# stm32103c8t6-v5.net
KiCad netlist of a schematic drawn in EAGLE
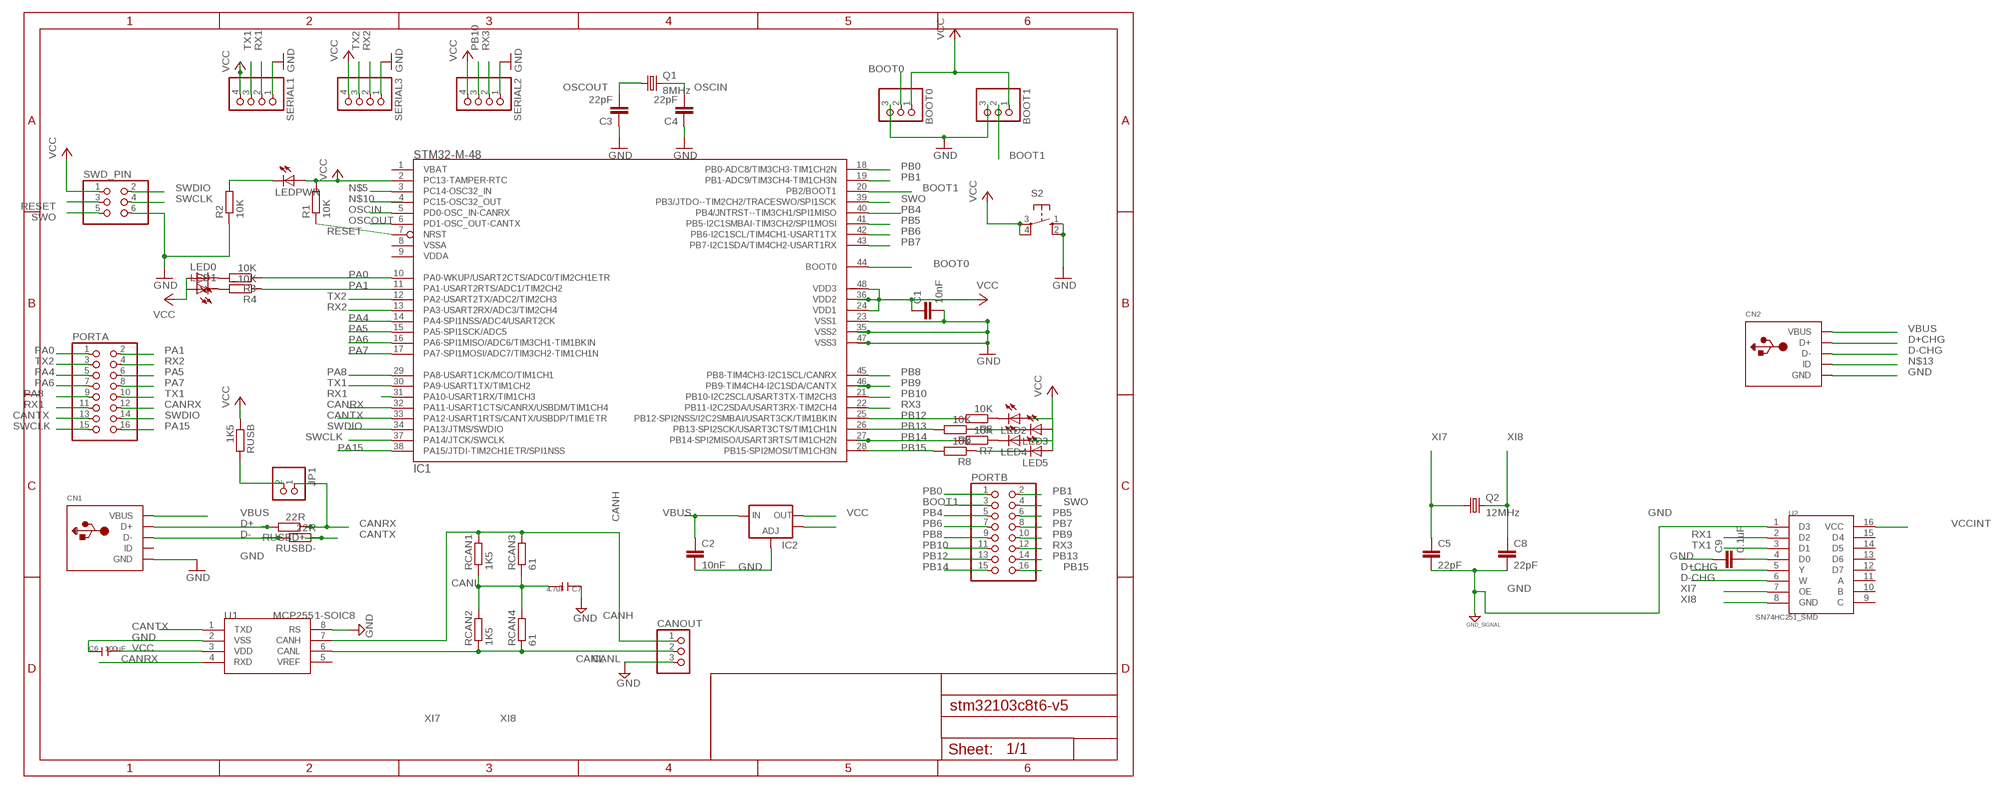
[diagram p0: schematic, sheet 1]

(export (version "E")
  (design (tool "Eeschema 10.0.6"))
  (components
    (comp (ref "BOOT0")
      (value "PINHD-1X3")
      (footprint "eagle-import:1X03")
      (libsource (lib "eagle-import") (part "PINHD-1X3"))
    )
    (comp (ref "BOOT1")
      (value "PINHD-1X3")
      (footprint "eagle-import:1X03")
      (libsource (lib "eagle-import") (part "PINHD-1X3"))
    )
    (comp (ref "C1")
      (value "10nF")
      (footprint "eagle-import:C1210")
      (libsource (lib "eagle-import") (part "C-EUC1210"))
    )
    (comp (ref "C2")
      (value "10nF")
      (footprint "eagle-import:C1206")
      (libsource (lib "eagle-import") (part "C-EUC1206"))
    )
    (comp (ref "C3")
      (value "22pF")
      (footprint "eagle-import:C1210")
      (libsource (lib "eagle-import") (part "C-EUC1210"))
    )
    (comp (ref "C4")
      (value "22pF")
      (footprint "eagle-import:C1210")
      (libsource (lib "eagle-import") (part "C-EUC1210"))
    )
    (comp (ref "C5")
      (value "22pF")
      (footprint "eagle-import:C1206")
      (libsource (lib "eagle-import") (part "C-EUC1206"))
    )
    (comp (ref "C6")
      (value "100uF")
      (footprint "eagle-import:C1206")
      (libsource (lib "eagle-import") (part "C-1206"))
    )
    (comp (ref "C7")
      (value "4.7uF")
      (footprint "eagle-import:C1206")
      (libsource (lib "eagle-import") (part "C-1206"))
    )
    (comp (ref "C8")
      (value "22pF")
      (footprint "eagle-import:C1206")
      (libsource (lib "eagle-import") (part "C-EUC1206"))
    )
    (comp (ref "C9")
      (value "0.1uF")
      (footprint "eagle-import:C1206")
      (libsource (lib "eagle-import") (part "C-EUC1206"))
    )
    (comp (ref "CANOUT")
      (value "PINHD-1X3")
      (footprint "eagle-import:1X03")
      (libsource (lib "eagle-import") (part "PINHD-1X3"))
    )
    (comp (ref "CN1")
      (value "USBTHM")
      (footprint "eagle-import:USB-MINIB-THM")
      (libsource (lib "eagle-import") (part "USBTHM"))
    )
    (comp (ref "CN2")
      (value "USBTHM")
      (footprint "eagle-import:USB-MINIB-THM")
      (libsource (lib "eagle-import") (part "USBTHM"))
    )
    (comp (ref "IC1")
      (value "STM32-M-48")
      (footprint "eagle-import:LQFP48")
      (libsource (lib "eagle-import") (part "STM32-M-48"))
    )
    (comp (ref "IC2")
      (value "V_REG_LM1117SOT223")
      (footprint "eagle-import:SOT223")
      (libsource (lib "eagle-import") (part "V_REG_LM1117SOT223"))
    )
    (comp (ref "JP1")
      (value "PINHD-1X2")
      (footprint "eagle-import:1X02")
      (libsource (lib "eagle-import") (part "PINHD-1X2"))
    )
    (comp (ref "LED0")
      (value "LEDSMT1206")
      (footprint "eagle-import:1206")
      (libsource (lib "eagle-import") (part "LEDSMT1206"))
    )
    (comp (ref "LED1")
      (value "LEDSMT1206")
      (footprint "eagle-import:1206")
      (libsource (lib "eagle-import") (part "LEDSMT1206"))
    )
    (comp (ref "LED2")
      (value "LEDSMT1206")
      (footprint "eagle-import:1206")
      (libsource (lib "eagle-import") (part "LEDSMT1206"))
    )
    (comp (ref "LED3")
      (value "LEDSMT1206")
      (footprint "eagle-import:1206")
      (libsource (lib "eagle-import") (part "LEDSMT1206"))
    )
    (comp (ref "LED4")
      (value "LEDSMT1206")
      (footprint "eagle-import:1206")
      (libsource (lib "eagle-import") (part "LEDSMT1206"))
    )
    (comp (ref "LED5")
      (value "LEDSMT1206")
      (footprint "eagle-import:1206")
      (libsource (lib "eagle-import") (part "LEDSMT1206"))
    )
    (comp (ref "LEDPWR")
      (value "LEDSMT1206")
      (footprint "eagle-import:1206")
      (libsource (lib "eagle-import") (part "LEDSMT1206"))
    )
    (comp (ref "PORTA")
      (value "PINHD-2X8")
      (footprint "eagle-import:2X08")
      (libsource (lib "eagle-import") (part "PINHD-2X8"))
    )
    (comp (ref "PORTB")
      (value "PINHD-2X8")
      (footprint "eagle-import:2X08")
      (libsource (lib "eagle-import") (part "PINHD-2X8"))
    )
    (comp (ref "Q1")
      (value "8MHz")
      (footprint "eagle-import:HC49_S")
      (libsource (lib "eagle-import") (part "CRYSTALHC49S"))
    )
    (comp (ref "Q2")
      (value "12MHz")
      (footprint "eagle-import:HC49_S")
      (libsource (lib "eagle-import") (part "CRYSTALHC49S"))
    )
    (comp (ref "R1")
      (value "10K")
      (footprint "eagle-import:R1206")
      (libsource (lib "eagle-import") (part "R-EU_R1206"))
    )
    (comp (ref "R2")
      (value "10K")
      (footprint "eagle-import:R1206")
      (libsource (lib "eagle-import") (part "R-EU_R1206"))
    )
    (comp (ref "R3")
      (value "10K")
      (footprint "eagle-import:R1206")
      (libsource (lib "eagle-import") (part "R-EU_R1206"))
    )
    (comp (ref "R4")
      (value "10K")
      (footprint "eagle-import:R1206")
      (libsource (lib "eagle-import") (part "R-EU_R1206"))
    )
    (comp (ref "R5")
      (value "10K")
      (footprint "eagle-import:R1206")
      (libsource (lib "eagle-import") (part "R-EU_R1206"))
    )
    (comp (ref "R6")
      (value "10K")
      (footprint "eagle-import:R1206")
      (libsource (lib "eagle-import") (part "R-EU_R1206"))
    )
    (comp (ref "R7")
      (value "10K")
      (footprint "eagle-import:R1206")
      (libsource (lib "eagle-import") (part "R-EU_R1206"))
    )
    (comp (ref "R8")
      (value "10K")
      (footprint "eagle-import:R1206")
      (libsource (lib "eagle-import") (part "R-EU_R1206"))
    )
    (comp (ref "RCAN1")
      (value "1K5")
      (footprint "eagle-import:R1206")
      (libsource (lib "eagle-import") (part "R-EU_R1206"))
    )
    (comp (ref "RCAN2")
      (value "1K5")
      (footprint "eagle-import:R1206")
      (libsource (lib "eagle-import") (part "R-EU_R1206"))
    )
    (comp (ref "RCAN3")
      (value "61")
      (footprint "eagle-import:R1206")
      (libsource (lib "eagle-import") (part "R-EU_R1206"))
    )
    (comp (ref "RCAN4")
      (value "61")
      (footprint "eagle-import:R1206")
      (libsource (lib "eagle-import") (part "R-EU_R1206"))
    )
    (comp (ref "RUSB")
      (value "1K5")
      (footprint "eagle-import:R1206")
      (libsource (lib "eagle-import") (part "R-EU_R1206"))
    )
    (comp (ref "RUSBD+")
      (value "22R")
      (footprint "eagle-import:R1206")
      (libsource (lib "eagle-import") (part "R-EU_R1206"))
    )
    (comp (ref "RUSBD-")
      (value "22R")
      (footprint "eagle-import:R1206")
      (libsource (lib "eagle-import") (part "R-EU_R1206"))
    )
    (comp (ref "S2")
      (value "10-XX")
      (footprint "eagle-import:B3F-10XX")
      (fields (field (name "MPN") "B3F-1000"))
      (libsource (lib "eagle-import") (part "10-XX"))
    )
    (comp (ref "SERIAL1")
      (value "PINHD-1X4")
      (footprint "eagle-import:1X04")
      (libsource (lib "eagle-import") (part "PINHD-1X4"))
    )
    (comp (ref "SERIAL2")
      (value "PINHD-1X4")
      (footprint "eagle-import:1X04")
      (libsource (lib "eagle-import") (part "PINHD-1X4"))
    )
    (comp (ref "SERIAL3")
      (value "PINHD-1X4")
      (footprint "eagle-import:1X04")
      (libsource (lib "eagle-import") (part "PINHD-1X4"))
    )
    (comp (ref "SWD_PIN")
      (value "PINHD-2X3")
      (footprint "eagle-import:2X03")
      (libsource (lib "eagle-import") (part "PINHD-2X3"))
    )
    (comp (ref "U1")
      (value "MCP2551-SOIC8")
      (footprint "eagle-import:SOIC8-6.0")
      (libsource (lib "eagle-import") (part "MCP2551-SOIC8"))
    )
    (comp (ref "U2")
      (value "SN74HC251_SMD")
      (footprint "eagle-import:SO016")
      (libsource (lib "eagle-import") (part "SN74HC251_SMD"))
    )
  )
  (nets
    (net (code "1") (name "/BOOT0") (class "Default")
      (node (ref "BOOT0") (pin "2") (pinfunction "2_2") (pintype "passive"))
      (node (ref "IC1") (pin "44") (pinfunction "BOOT0_44") (pintype "input"))
    )
    (net (code "2") (name "/BOOT1") (class "Default")
      (node (ref "BOOT1") (pin "2") (pinfunction "2_2") (pintype "passive"))
      (node (ref "IC1") (pin "20") (pinfunction "PB2/BOOT1_20") (pintype "bidirectional"))
      (node (ref "PORTB") (pin "3") (pinfunction "3_3") (pintype "passive"))
    )
    (net (code "3") (name "/CANH") (class "Default")
      (node (ref "CANOUT") (pin "1") (pinfunction "1_1") (pintype "passive"))
      (node (ref "RCAN1") (pin "2") (pinfunction "2_2") (pintype "passive"))
      (node (ref "RCAN3") (pin "2") (pinfunction "2_2") (pintype "passive"))
      (node (ref "U1") (pin "7") (pinfunction "CANH_7") (pintype "bidirectional"))
    )
    (net (code "4") (name "/CANL") (class "Default")
      (node (ref "CANOUT") (pin "2") (pinfunction "2_2") (pintype "passive"))
      (node (ref "RCAN2") (pin "1") (pinfunction "1_1") (pintype "passive"))
      (node (ref "RCAN4") (pin "1") (pinfunction "1_1") (pintype "passive"))
      (node (ref "U1") (pin "6") (pinfunction "CANL_6") (pintype "bidirectional"))
    )
    (net (code "5") (name "/CANRX") (class "Default")
      (node (ref "IC1") (pin "32") (pinfunction "PA11-USART1CTS/CANRX/USBDM/TIM1CH4_32") (pintype "bidirectional"))
      (node (ref "JP1") (pin "1") (pinfunction "1_1") (pintype "passive"))
      (node (ref "PORTA") (pin "12") (pinfunction "12_12") (pintype "passive"))
      (node (ref "RUSBD+") (pin "1") (pinfunction "1_1") (pintype "passive"))
      (node (ref "U1") (pin "4") (pinfunction "RXD_4") (pintype "bidirectional"))
    )
    (net (code "6") (name "/CANTX") (class "Default")
      (node (ref "IC1") (pin "33") (pinfunction "PA12-USART1RTS/CANTX/USBDP/TIM1ETR_33") (pintype "bidirectional"))
      (node (ref "PORTA") (pin "13") (pinfunction "13_13") (pintype "passive"))
      (node (ref "RUSBD-") (pin "1") (pinfunction "1_1") (pintype "passive"))
      (node (ref "U1") (pin "1") (pinfunction "TXD_1") (pintype "bidirectional"))
    )
    (net (code "7") (name "/D+") (class "Default")
      (node (ref "CN1") (pin "D+") (pinfunction "D+_D+") (pintype "bidirectional"))
      (node (ref "RUSBD+") (pin "2") (pinfunction "2_2") (pintype "passive"))
    )
    (net (code "8") (name "/D+CHG") (class "Default")
      (node (ref "CN2") (pin "D+") (pinfunction "D+_D+") (pintype "bidirectional"))
      (node (ref "U2") (pin "5") (pinfunction "Y_5") (pintype "bidirectional"))
    )
    (net (code "9") (name "/D-") (class "Default")
      (node (ref "CN1") (pin "D-") (pinfunction "D-_D-") (pintype "bidirectional"))
      (node (ref "RUSBD-") (pin "2") (pinfunction "2_2") (pintype "passive"))
    )
    (net (code "10") (name "/D-CHG") (class "Default")
      (node (ref "CN2") (pin "D-") (pinfunction "D-_D-") (pintype "bidirectional"))
      (node (ref "U2") (pin "6") (pinfunction "W_6") (pintype "bidirectional"))
    )
    (net (code "11") (name "/N$5") (class "Default")
      (node (ref "IC1") (pin "3") (pinfunction "PC14-OSC32_IN_3") (pintype "bidirectional"))
    )
    (net (code "13") (name "/N$13") (class "Default")
      (node (ref "CN2") (pin "ID") (pinfunction "ID_ID") (pintype "bidirectional"))
    )
    (net (code "14") (name "/OSCIN") (class "Default")
      (node (ref "C4") (pin "2") (pinfunction "2_2") (pintype "passive"))
      (node (ref "IC1") (pin "5") (pinfunction "PD0-OSC_IN-CANRX_5") (pintype "input"))
      (node (ref "Q1") (pin "2") (pinfunction "2_2") (pintype "passive"))
    )
    (net (code "15") (name "/OSCOUT") (class "Default")
      (node (ref "C3") (pin "2") (pinfunction "2_2") (pintype "passive"))
      (node (ref "IC1") (pin "6") (pinfunction "PD1-OSC_OUT-CANTX_6") (pintype "output"))
      (node (ref "Q1") (pin "1") (pinfunction "1_1") (pintype "passive"))
    )
    (net (code "16") (name "/PA0") (class "Default")
      (node (ref "IC1") (pin "10") (pinfunction "PA0-WKUP/USART2CTS/ADC0/TIM2CH1ETR_10") (pintype "bidirectional"))
      (node (ref "PORTA") (pin "1") (pinfunction "1_1") (pintype "passive"))
      (node (ref "R3") (pin "1") (pinfunction "1_1") (pintype "passive"))
    )
    (net (code "17") (name "/PA1") (class "Default")
      (node (ref "IC1") (pin "11") (pinfunction "PA1-USART2RTS/ADC1/TIM2CH2_11") (pintype "bidirectional"))
      (node (ref "PORTA") (pin "2") (pinfunction "2_2") (pintype "passive"))
      (node (ref "R4") (pin "1") (pinfunction "1_1") (pintype "passive"))
    )
    (net (code "18") (name "/PA4") (class "Default")
      (node (ref "IC1") (pin "14") (pinfunction "PA4-SPI1NSS/ADC4/USART2CK_14") (pintype "bidirectional"))
      (node (ref "PORTA") (pin "5") (pinfunction "5_5") (pintype "passive"))
    )
    (net (code "19") (name "/PA5") (class "Default")
      (node (ref "IC1") (pin "15") (pinfunction "PA5-SPI1SCK/ADC5_15") (pintype "bidirectional"))
      (node (ref "PORTA") (pin "6") (pinfunction "6_6") (pintype "passive"))
    )
    (net (code "20") (name "/PA6") (class "Default")
      (node (ref "IC1") (pin "16") (pinfunction "PA6-SPI1MISO/ADC6/TIM3CH1-TIM1BKIN_16") (pintype "bidirectional"))
      (node (ref "PORTA") (pin "7") (pinfunction "7_7") (pintype "passive"))
    )
    (net (code "21") (name "/PA7") (class "Default")
      (node (ref "IC1") (pin "17") (pinfunction "PA7-SPI1MOSI/ADC7/TIM3CH2-TIM1CH1N_17") (pintype "bidirectional"))
      (node (ref "PORTA") (pin "8") (pinfunction "8_8") (pintype "passive"))
    )
    (net (code "22") (name "/PA8") (class "Default")
      (node (ref "IC1") (pin "29") (pinfunction "PA8-USART1CK/MCO/TIM1CH1_29") (pintype "bidirectional"))
      (node (ref "PORTA") (pin "9") (pinfunction "9_9") (pintype "passive"))
    )
    (net (code "23") (name "/PA15") (class "Default")
      (node (ref "IC1") (pin "38") (pinfunction "PA15/JTDI-TIM2CH1ETR/SPI1NSS_38") (pintype "bidirectional"))
      (node (ref "PORTA") (pin "16") (pinfunction "16_16") (pintype "passive"))
    )
    (net (code "24") (name "/PB0") (class "Default")
      (node (ref "IC1") (pin "18") (pinfunction "PB0-ADC8/TIM3CH3-TIM1CH2N_18") (pintype "bidirectional"))
      (node (ref "PORTB") (pin "1") (pinfunction "1_1") (pintype "passive"))
    )
    (net (code "25") (name "/PB1") (class "Default")
      (node (ref "IC1") (pin "19") (pinfunction "PB1-ADC9/TIM3CH4-TIM1CH3N_19") (pintype "bidirectional"))
      (node (ref "PORTB") (pin "2") (pinfunction "2_2") (pintype "passive"))
    )
    (net (code "26") (name "/PB4") (class "Default")
      (node (ref "IC1") (pin "40") (pinfunction "PB4/JNTRST--TIM3CH1/SPI1MISO_40") (pintype "bidirectional"))
      (node (ref "PORTB") (pin "5") (pinfunction "5_5") (pintype "passive"))
    )
    (net (code "27") (name "/PB5") (class "Default")
      (node (ref "IC1") (pin "41") (pinfunction "PB5-I2C1SMBAI-TIM3CH2/SPI1MOSI_41") (pintype "bidirectional"))
      (node (ref "PORTB") (pin "6") (pinfunction "6_6") (pintype "passive"))
    )
    (net (code "28") (name "/PB6") (class "Default")
      (node (ref "IC1") (pin "42") (pinfunction "PB6-I2C1SCL/TIM4CH1-USART1TX_42") (pintype "bidirectional"))
      (node (ref "PORTB") (pin "7") (pinfunction "7_7") (pintype "passive"))
    )
    (net (code "29") (name "/PB7") (class "Default")
      (node (ref "IC1") (pin "43") (pinfunction "PB7-I2C1SDA/TIM4CH2-USART1RX_43") (pintype "bidirectional"))
      (node (ref "PORTB") (pin "8") (pinfunction "8_8") (pintype "passive"))
    )
    (net (code "30") (name "/PB8") (class "Default")
      (node (ref "IC1") (pin "45") (pinfunction "PB8-TIM4CH3-I2C1SCL/CANRX_45") (pintype "bidirectional"))
      (node (ref "PORTB") (pin "9") (pinfunction "9_9") (pintype "passive"))
    )
    (net (code "31") (name "/PB9") (class "Default")
      (node (ref "IC1") (pin "46") (pinfunction "PB9-TIM4CH4-I2C1SDA/CANTX_46") (pintype "bidirectional"))
      (node (ref "PORTB") (pin "10") (pinfunction "10_10") (pintype "passive"))
    )
    (net (code "32") (name "/PB10") (class "Default")
      (node (ref "IC1") (pin "21") (pinfunction "PB10-I2C2SCL/USART3TX-TIM2CH3_21") (pintype "bidirectional"))
      (node (ref "PORTB") (pin "11") (pinfunction "11_11") (pintype "passive"))
      (node (ref "SERIAL2") (pin "3") (pinfunction "3_3") (pintype "passive"))
    )
    (net (code "33") (name "/PB12") (class "Default")
      (node (ref "IC1") (pin "25") (pinfunction "PB12-SPI2NSS/I2C2SMBAI/USART3CK/TIM1BKIN_25") (pintype "bidirectional"))
      (node (ref "PORTB") (pin "13") (pinfunction "13_13") (pintype "passive"))
      (node (ref "R5") (pin "2") (pinfunction "2_2") (pintype "passive"))
    )
    (net (code "34") (name "/PB13") (class "Default")
      (node (ref "IC1") (pin "26") (pinfunction "PB13-SPI2SCK/USART3CTS/TIM1CH1N_26") (pintype "bidirectional"))
      (node (ref "PORTB") (pin "14") (pinfunction "14_14") (pintype "passive"))
      (node (ref "R6") (pin "2") (pinfunction "2_2") (pintype "passive"))
    )
    (net (code "35") (name "/PB14") (class "Default")
      (node (ref "IC1") (pin "27") (pinfunction "PB14-SPI2MISO/USART3RTS/TIM1CH2N_27") (pintype "bidirectional"))
      (node (ref "PORTB") (pin "15") (pinfunction "15_15") (pintype "passive"))
      (node (ref "R7") (pin "2") (pinfunction "2_2") (pintype "passive"))
    )
    (net (code "36") (name "/PB15") (class "Default")
      (node (ref "IC1") (pin "28") (pinfunction "PB15-SPI2MOSI/TIM1CH3N_28") (pintype "bidirectional"))
      (node (ref "PORTB") (pin "16") (pinfunction "16_16") (pintype "passive"))
      (node (ref "R8") (pin "2") (pinfunction "2_2") (pintype "passive"))
    )
    (net (code "37") (name "/RESET") (class "Default")
      (node (ref "IC1") (pin "7") (pinfunction "NRST_7") (pintype "bidirectional"))
      (node (ref "R1") (pin "1") (pinfunction "1_1") (pintype "passive"))
      (node (ref "SWD_PIN") (pin "3") (pinfunction "3_3") (pintype "passive"))
    )
    (net (code "38") (name "/RX1") (class "Default")
      (node (ref "IC1") (pin "31") (pinfunction "PA10-USART1RX/TIM1CH3_31") (pintype "bidirectional"))
      (node (ref "PORTA") (pin "11") (pinfunction "11_11") (pintype "passive"))
      (node (ref "SERIAL1") (pin "2") (pinfunction "2_2") (pintype "passive"))
      (node (ref "U2") (pin "2") (pinfunction "D2_2") (pintype "bidirectional"))
    )
    (net (code "39") (name "/RX2") (class "Default")
      (node (ref "IC1") (pin "13") (pinfunction "PA3-USART2RX/ADC3/TIM2CH4_13") (pintype "bidirectional"))
      (node (ref "PORTA") (pin "4") (pinfunction "4_4") (pintype "passive"))
      (node (ref "SERIAL3") (pin "2") (pinfunction "2_2") (pintype "passive"))
    )
    (net (code "40") (name "/RX3") (class "Default")
      (node (ref "IC1") (pin "22") (pinfunction "PB11-I2C2SDA/USART3RX-TIM2CH4_22") (pintype "bidirectional"))
      (node (ref "PORTB") (pin "12") (pinfunction "12_12") (pintype "passive"))
      (node (ref "SERIAL2") (pin "2") (pinfunction "2_2") (pintype "passive"))
    )
    (net (code "41") (name "/SWCLK") (class "Default")
      (node (ref "IC1") (pin "37") (pinfunction "PA14/JTCK/SWCLK_37") (pintype "bidirectional"))
      (node (ref "PORTA") (pin "15") (pinfunction "15_15") (pintype "passive"))
      (node (ref "SWD_PIN") (pin "4") (pinfunction "4_4") (pintype "passive"))
    )
    (net (code "42") (name "/SWDIO") (class "Default")
      (node (ref "IC1") (pin "34") (pinfunction "PA13/JTMS/SWDIO_34") (pintype "bidirectional"))
      (node (ref "PORTA") (pin "14") (pinfunction "14_14") (pintype "passive"))
      (node (ref "SWD_PIN") (pin "2") (pinfunction "2_2") (pintype "passive"))
    )
    (net (code "43") (name "/SWO") (class "Default")
      (node (ref "IC1") (pin "39") (pinfunction "PB3/JTDO--TIM2CH2/TRACESWO/SPI1SCK_39") (pintype "bidirectional"))
      (node (ref "PORTB") (pin "4") (pinfunction "4_4") (pintype "passive"))
      (node (ref "SWD_PIN") (pin "5") (pinfunction "5_5") (pintype "passive"))
    )
    (net (code "44") (name "/TX1") (class "Default")
      (node (ref "IC1") (pin "30") (pinfunction "PA9-USART1TX/TIM1CH2_30") (pintype "bidirectional"))
      (node (ref "PORTA") (pin "10") (pinfunction "10_10") (pintype "passive"))
      (node (ref "SERIAL1") (pin "3") (pinfunction "3_3") (pintype "passive"))
      (node (ref "U2") (pin "3") (pinfunction "D1_3") (pintype "bidirectional"))
    )
    (net (code "45") (name "/TX2") (class "Default")
      (node (ref "IC1") (pin "12") (pinfunction "PA2-USART2TX/ADC2/TIM2CH3_12") (pintype "bidirectional"))
      (node (ref "PORTA") (pin "3") (pinfunction "3_3") (pintype "passive"))
      (node (ref "SERIAL3") (pin "3") (pinfunction "3_3") (pintype "passive"))
    )
    (net (code "46") (name "/VBAT") (class "Default")
      (node (ref "IC1") (pin "1") (pinfunction "VBAT_1") (pintype "power_in"))
    )
    (net (code "47") (name "/VBUS") (class "Default")
      (node (ref "C2") (pin "1") (pinfunction "1_1") (pintype "passive"))
      (node (ref "CN1") (pin "VBUS") (pinfunction "VBUS_VBUS") (pintype "power_in"))
      (node (ref "CN2") (pin "VBUS") (pinfunction "VBUS_VBUS") (pintype "power_in"))
      (node (ref "IC2") (pin "3") (pinfunction "IN_3") (pintype "input"))
    )
    (net (code "48") (name "/VCCINT") (class "Default")
      (node (ref "U2") (pin "16") (pinfunction "VCC_16") (pintype "bidirectional"))
    )
    (net (code "49") (name "/VDDA") (class "Default")
      (node (ref "IC1") (pin "9") (pinfunction "VDDA_9") (pintype "power_in"))
    )
    (net (code "50") (name "/VSSA") (class "Default")
      (node (ref "IC1") (pin "8") (pinfunction "VSSA_8") (pintype "power_in"))
    )
    (net (code "51") (name "/XI7") (class "Default")
      (node (ref "C5") (pin "1") (pinfunction "1_1") (pintype "passive"))
      (node (ref "Q2") (pin "1") (pinfunction "1_1") (pintype "passive"))
      (node (ref "U2") (pin "7") (pinfunction "OE_7") (pintype "bidirectional"))
    )
    (net (code "52") (name "/XI8") (class "Default")
      (node (ref "C8") (pin "1") (pinfunction "1_1") (pintype "passive"))
      (node (ref "Q2") (pin "2") (pinfunction "2_2") (pintype "passive"))
      (node (ref "U2") (pin "8") (pinfunction "GND_8") (pintype "bidirectional"))
    )
    (net (code "53") (name "GND") (class "Default")
      (node (ref "BOOT0") (pin "3") (pinfunction "3_3") (pintype "passive"))
      (node (ref "BOOT1") (pin "3") (pinfunction "3_3") (pintype "passive"))
      (node (ref "C1") (pin "2") (pinfunction "2_2") (pintype "passive"))
      (node (ref "C2") (pin "2") (pinfunction "2_2") (pintype "passive"))
      (node (ref "C3") (pin "1") (pinfunction "1_1") (pintype "passive"))
      (node (ref "C4") (pin "1") (pinfunction "1_1") (pintype "passive"))
      (node (ref "C5") (pin "2") (pinfunction "2_2") (pintype "passive"))
      (node (ref "C6") (pin "1") (pinfunction "1_1") (pintype "passive"))
      (node (ref "C7") (pin "1") (pinfunction "1_1") (pintype "passive"))
      (node (ref "C8") (pin "2") (pinfunction "2_2") (pintype "passive"))
      (node (ref "C9") (pin "1") (pinfunction "1_1") (pintype "passive"))
      (node (ref "CANOUT") (pin "3") (pinfunction "3_3") (pintype "passive"))
      (node (ref "CN1") (pin "GND") (pinfunction "GND_GND") (pintype "power_in"))
      (node (ref "CN2") (pin "GND") (pinfunction "GND_GND") (pintype "power_in"))
      (node (ref "IC1") (pin "23") (pinfunction "VSS1_23") (pintype "power_in"))
      (node (ref "IC1") (pin "35") (pinfunction "VSS2_35") (pintype "power_in"))
      (node (ref "IC1") (pin "47") (pinfunction "VSS3_47") (pintype "power_in"))
      (node (ref "IC2") (pin "1") (pinfunction "ADJ_1") (pintype "input"))
      (node (ref "R2") (pin "1") (pinfunction "1_1") (pintype "passive"))
      (node (ref "S2") (pin "1") (pinfunction "S_1") (pintype "passive"))
      (node (ref "S2") (pin "2") (pinfunction "S1_2") (pintype "passive"))
      (node (ref "SERIAL1") (pin "1") (pinfunction "1_1") (pintype "passive"))
      (node (ref "SERIAL2") (pin "1") (pinfunction "1_1") (pintype "passive"))
      (node (ref "SERIAL3") (pin "1") (pinfunction "1_1") (pintype "passive"))
      (node (ref "SWD_PIN") (pin "6") (pinfunction "6_6") (pintype "passive"))
      (node (ref "U1") (pin "2") (pinfunction "VSS_2") (pintype "bidirectional"))
      (node (ref "U1") (pin "8") (pinfunction "RS_8") (pintype "bidirectional"))
      (node (ref "U2") (pin "1") (pinfunction "D3_1") (pintype "bidirectional"))
    )
    (net (code "54") (name "Net-(C7-Pad2)") (class "Default")
      (node (ref "C7") (pin "2") (pinfunction "2_2") (pintype "passive"))
      (node (ref "RCAN1") (pin "1") (pinfunction "1_1") (pintype "passive"))
      (node (ref "RCAN2") (pin "2") (pinfunction "2_2") (pintype "passive"))
      (node (ref "RCAN3") (pin "1") (pinfunction "1_1") (pintype "passive"))
      (node (ref "RCAN4") (pin "2") (pinfunction "2_2") (pintype "passive"))
    )
    (net (code "55") (name "Net-(JP1-Pad2)") (class "Default")
      (node (ref "JP1") (pin "2") (pinfunction "2_2") (pintype "passive"))
      (node (ref "RUSB") (pin "2") (pinfunction "2_2") (pintype "passive"))
    )
    (net (code "56") (name "Net-(LED0-PadC)") (class "Default")
      (node (ref "LED0") (pin "C") (pinfunction "C_C") (pintype "passive"))
      (node (ref "R3") (pin "2") (pinfunction "2_2") (pintype "passive"))
    )
    (net (code "57") (name "Net-(LED1-PadC)") (class "Default")
      (node (ref "LED1") (pin "C") (pinfunction "C_C") (pintype "passive"))
      (node (ref "R4") (pin "2") (pinfunction "2_2") (pintype "passive"))
    )
    (net (code "58") (name "Net-(LED2-PadC)") (class "Default")
      (node (ref "LED2") (pin "C") (pinfunction "C_C") (pintype "passive"))
      (node (ref "R5") (pin "1") (pinfunction "1_1") (pintype "passive"))
    )
    (net (code "59") (name "Net-(LED3-PadC)") (class "Default")
      (node (ref "LED3") (pin "C") (pinfunction "C_C") (pintype "passive"))
      (node (ref "R6") (pin "1") (pinfunction "1_1") (pintype "passive"))
    )
    (net (code "60") (name "Net-(LED4-PadC)") (class "Default")
      (node (ref "LED4") (pin "C") (pinfunction "C_C") (pintype "passive"))
      (node (ref "R7") (pin "1") (pinfunction "1_1") (pintype "passive"))
    )
    (net (code "61") (name "Net-(LED5-PadC)") (class "Default")
      (node (ref "LED5") (pin "C") (pinfunction "C_C") (pintype "passive"))
      (node (ref "R8") (pin "1") (pinfunction "1_1") (pintype "passive"))
    )
    (net (code "62") (name "Net-(LEDPWR-PadC)") (class "Default")
      (node (ref "LEDPWR") (pin "C") (pinfunction "C_C") (pintype "passive"))
      (node (ref "R2") (pin "2") (pinfunction "2_2") (pintype "passive"))
    )
    (net (code "63") (name "Net-(U2-D0)") (class "Default")
      (node (ref "C9") (pin "2") (pinfunction "2_2") (pintype "passive"))
      (node (ref "U2") (pin "4") (pinfunction "D0_4") (pintype "bidirectional"))
    )
    (net (code "64") (name "VCC") (class "Default")
      (node (ref "BOOT0") (pin "1") (pinfunction "1_1") (pintype "passive"))
      (node (ref "BOOT1") (pin "1") (pinfunction "1_1") (pintype "passive"))
      (node (ref "C1") (pin "1") (pinfunction "1_1") (pintype "passive"))
      (node (ref "C6") (pin "2") (pinfunction "2_2") (pintype "passive"))
      (node (ref "IC1") (pin "2") (pinfunction "PC13-TAMPER-RTC_2") (pintype "bidirectional"))
      (node (ref "IC1") (pin "24") (pinfunction "VDD1_24") (pintype "power_in"))
      (node (ref "IC1") (pin "36") (pinfunction "VDD2_36") (pintype "power_in"))
      (node (ref "IC1") (pin "48") (pinfunction "VDD3_48") (pintype "power_in"))
      (node (ref "IC2") (pin "2") (pinfunction "OUT_2") (pintype "output"))
      (node (ref "LED0") (pin "A") (pinfunction "A_A") (pintype "passive"))
      (node (ref "LED1") (pin "A") (pinfunction "A_A") (pintype "passive"))
      (node (ref "LED2") (pin "A") (pinfunction "A_A") (pintype "passive"))
      (node (ref "LED3") (pin "A") (pinfunction "A_A") (pintype "passive"))
      (node (ref "LED4") (pin "A") (pinfunction "A_A") (pintype "passive"))
      (node (ref "LED5") (pin "A") (pinfunction "A_A") (pintype "passive"))
      (node (ref "LEDPWR") (pin "A") (pinfunction "A_A") (pintype "passive"))
      (node (ref "R1") (pin "2") (pinfunction "2_2") (pintype "passive"))
      (node (ref "RUSB") (pin "1") (pinfunction "1_1") (pintype "passive"))
      (node (ref "S2") (pin "3") (pinfunction "P_3") (pintype "passive"))
      (node (ref "S2") (pin "4") (pinfunction "P1_4") (pintype "passive"))
      (node (ref "SERIAL1") (pin "4") (pinfunction "4_4") (pintype "passive"))
      (node (ref "SERIAL2") (pin "4") (pinfunction "4_4") (pintype "passive"))
      (node (ref "SERIAL3") (pin "4") (pinfunction "4_4") (pintype "passive"))
      (node (ref "SWD_PIN") (pin "1") (pinfunction "1_1") (pintype "passive"))
      (node (ref "U1") (pin "3") (pinfunction "VDD_3") (pintype "bidirectional"))
    )
    (net (code "65") (name "unconnected-(CN1-PadID)") (class "Default")
      (node (ref "CN1") (pin "ID") (pinfunction "ID_ID") (pintype "bidirectional"))
    )
    (net (code "66") (name "unconnected-(IC1-PC15-OSC32_OUT-Pad4)") (class "Default")
      (node (ref "IC1") (pin "4") (pinfunction "PC15-OSC32_OUT_4") (pintype "bidirectional"))
    )
    (net (code "67") (name "unconnected-(IC2-OUT-Pad4)") (class "Default")
      (node (ref "IC2") (pin "4") (pinfunction "OUT_4") (pintype "output"))
    )
    (net (code "68") (name "unconnected-(U1-VREF-Pad5)") (class "Default")
      (node (ref "U1") (pin "5") (pinfunction "VREF_5") (pintype "bidirectional"))
    )
    (net (code "69") (name "unconnected-(U2-A-Pad11)") (class "Default")
      (node (ref "U2") (pin "11") (pinfunction "A_11") (pintype "bidirectional"))
    )
    (net (code "70") (name "unconnected-(U2-B-Pad10)") (class "Default")
      (node (ref "U2") (pin "10") (pinfunction "B_10") (pintype "bidirectional"))
    )
    (net (code "71") (name "unconnected-(U2-C-Pad9)") (class "Default")
      (node (ref "U2") (pin "9") (pinfunction "C_9") (pintype "bidirectional"))
    )
    (net (code "72") (name "unconnected-(U2-D4-Pad15)") (class "Default")
      (node (ref "U2") (pin "15") (pinfunction "D4_15") (pintype "bidirectional"))
    )
    (net (code "73") (name "unconnected-(U2-D5-Pad14)") (class "Default")
      (node (ref "U2") (pin "14") (pinfunction "D5_14") (pintype "bidirectional"))
    )
    (net (code "74") (name "unconnected-(U2-D6-Pad13)") (class "Default")
      (node (ref "U2") (pin "13") (pinfunction "D6_13") (pintype "bidirectional"))
    )
    (net (code "75") (name "unconnected-(U2-D7-Pad12)") (class "Default")
      (node (ref "U2") (pin "12") (pinfunction "D7_12") (pintype "bidirectional"))
    )
  )
)
